# mainboard6.net
KiCad netlist of a schematic drawn in EAGLE
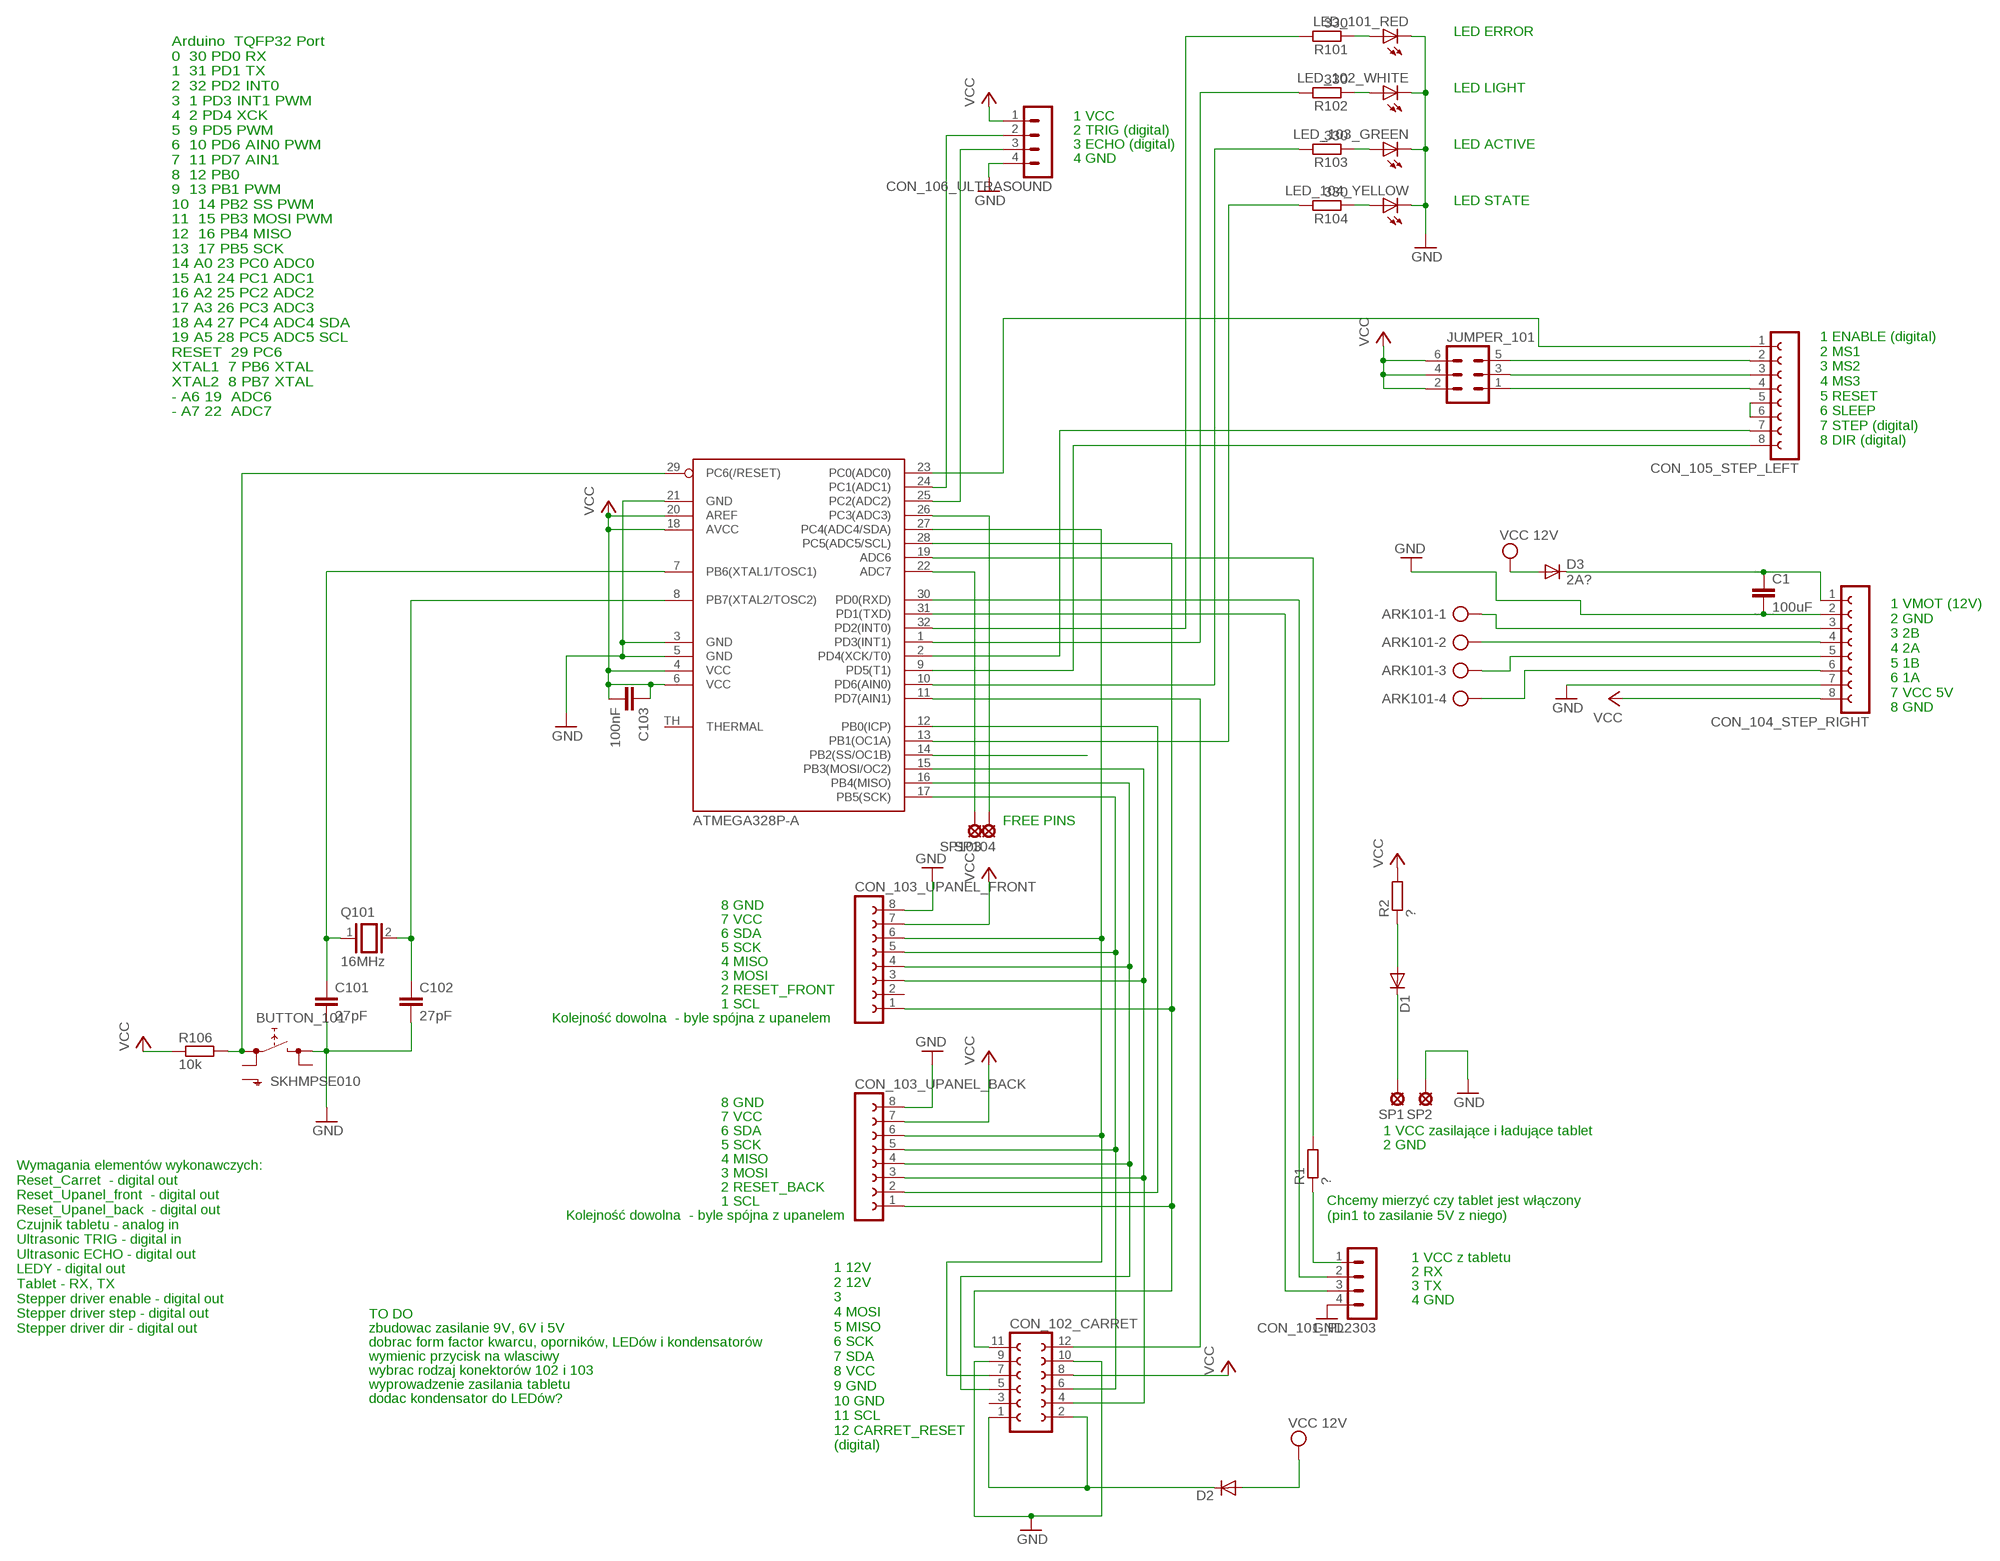
[diagram p0: schematic, sheet 1]

(export (version "E")
  (design (tool "Eeschema 10.0.6"))
  (components
    (comp (ref "ARK101")
      (value "AK300/4")
      (footprint "eagle-import:AK300_4")
      (libsource (lib "eagle-import") (part "AK300/4"))
    )
    (comp (ref "ATMEGA328P-A")
      (value "MEGA8-MI")
      (footprint "eagle-import:MLF32-TH")
      (libsource (lib "eagle-import") (part "MEGA8-MI"))
    )
    (comp (ref "BUTTON_101")
      (value "SKHMPSE010")
      (footprint "eagle-import:SKHMPXE010")
      (libsource (lib "eagle-import") (part "SKHMPE010S"))
    )
    (comp (ref "C1")
      (value "100uF")
      (footprint "eagle-import:C0805")
      (libsource (lib "eagle-import") (part "C"))
    )
    (comp (ref "C101")
      (value "27pF")
      (footprint "eagle-import:C5B5")
      (libsource (lib "eagle-import") (part "C5/5"))
    )
    (comp (ref "C102")
      (value "27pF")
      (footprint "eagle-import:C5B5")
      (libsource (lib "eagle-import") (part "C5/5"))
    )
    (comp (ref "C103")
      (value "100nF")
      (footprint "eagle-import:C5B5")
      (libsource (lib "eagle-import") (part "C5/5"))
    )
    (comp (ref "CON_101_PL2303")
      (value "MA04-1")
      (footprint "eagle-import:MA04-1")
      (libsource (lib "eagle-import") (part "MA04-1"))
    )
    (comp (ref "CON_102_CARRET")
      (value "FE06-2")
      (footprint "eagle-import:FE06-2")
      (libsource (lib "eagle-import") (part "FE06-2"))
    )
    (comp (ref "CON_103_UPANEL_BACK")
      (value "FE08-1")
      (footprint "eagle-import:FE08")
      (libsource (lib "eagle-import") (part "FE08-1"))
    )
    (comp (ref "CON_103_UPANEL_FRONT")
      (value "FE08-1")
      (footprint "eagle-import:FE08")
      (libsource (lib "eagle-import") (part "FE08-1"))
    )
    (comp (ref "CON_104_STEP_RIGHT")
      (value "FE08-1")
      (footprint "eagle-import:FE08")
      (libsource (lib "eagle-import") (part "FE08-1"))
    )
    (comp (ref "CON_105_STEP_LEFT")
      (value "FE08-1")
      (footprint "eagle-import:FE08")
      (libsource (lib "eagle-import") (part "FE08-1"))
    )
    (comp (ref "CON_106_ULTRASOUND")
      (value "MA04-1")
      (footprint "eagle-import:MA04-1")
      (libsource (lib "eagle-import") (part "MA04-1"))
    )
    (comp (ref "D1")
      (value "1N5060GP")
      (footprint "eagle-import:DO15-12")
      (libsource (lib "eagle-import") (part "1N5060GP"))
    )
    (comp (ref "D2")
      (value "1N5060GP")
      (footprint "eagle-import:DO15-12")
      (libsource (lib "eagle-import") (part "1N5060GP"))
    )
    (comp (ref "D3")
      (value "2A?")
      (footprint "eagle-import:DO15-12")
      (libsource (lib "eagle-import") (part "1N5060GP"))
    )
    (comp (ref "JUMPER_101")
      (value "MA03-2")
      (footprint "eagle-import:MA03-2")
      (libsource (lib "eagle-import") (part "MA03-2"))
    )
    (comp (ref "LED_101_RED")
      (value "LEDCHIPLED_1206")
      (footprint "eagle-import:CHIPLED_1206")
      (libsource (lib "eagle-import") (part "LEDCHIPLED_1206"))
    )
    (comp (ref "LED_102_WHITE")
      (value "LEDCHIPLED_1206")
      (footprint "eagle-import:CHIPLED_1206")
      (libsource (lib "eagle-import") (part "LEDCHIPLED_1206"))
    )
    (comp (ref "LED_103_GREEN")
      (value "LEDCHIPLED_1206")
      (footprint "eagle-import:CHIPLED_1206")
      (libsource (lib "eagle-import") (part "LEDCHIPLED_1206"))
    )
    (comp (ref "LED_104_YELLOW")
      (value "LEDCHIPLED_1206")
      (footprint "eagle-import:CHIPLED_1206")
      (libsource (lib "eagle-import") (part "LEDCHIPLED_1206"))
    )
    (comp (ref "Q101")
      (value "16MHz")
      (footprint "eagle-import:QS")
      (libsource (lib "eagle-import") (part "XTAL/S"))
    )
    (comp (ref "R1")
      (value "?")
      (footprint "eagle-import:P0613_15")
      (libsource (lib "eagle-import") (part "R-EU_0613/15"))
    )
    (comp (ref "R2")
      (value "?")
      (footprint "eagle-import:P0613_15")
      (libsource (lib "eagle-import") (part "R-EU_0613/15"))
    )
    (comp (ref "R101")
      (value "330")
      (footprint "eagle-import:M0805")
      (libsource (lib "eagle-import") (part "R-EU_M0805"))
    )
    (comp (ref "R102")
      (value "330")
      (footprint "eagle-import:M0805")
      (libsource (lib "eagle-import") (part "R-EU_M0805"))
    )
    (comp (ref "R103")
      (value "330")
      (footprint "eagle-import:M0805")
      (libsource (lib "eagle-import") (part "R-EU_M0805"))
    )
    (comp (ref "R104")
      (value "330")
      (footprint "eagle-import:M0805")
      (libsource (lib "eagle-import") (part "R-EU_M0805"))
    )
    (comp (ref "R106")
      (value "10k")
      (footprint "eagle-import:M3516")
      (libsource (lib "eagle-import") (part "R-EU_M3516"))
    )
    (comp (ref "SP1")
      (value "LSP11")
      (footprint "eagle-import:LSP11")
      (libsource (lib "eagle-import") (part "LSP11"))
    )
    (comp (ref "SP2")
      (value "LSP11")
      (footprint "eagle-import:LSP11")
      (libsource (lib "eagle-import") (part "LSP11"))
    )
    (comp (ref "SP103")
      (value "LSP11")
      (footprint "eagle-import:LSP11")
      (libsource (lib "eagle-import") (part "LSP11"))
    )
    (comp (ref "SP104")
      (value "LSP11")
      (footprint "eagle-import:LSP11")
      (libsource (lib "eagle-import") (part "LSP11"))
    )
  )
  (nets
    (net (code "1") (name "GND") (class "Default")
      (node (ref "ATMEGA328P-A") (pin "21") (pinfunction "GND_21") (pintype "power_in"))
      (node (ref "ATMEGA328P-A") (pin "3") (pinfunction "GND_3") (pintype "power_in"))
      (node (ref "ATMEGA328P-A") (pin "5") (pinfunction "GND_5") (pintype "power_in"))
      (node (ref "BUTTON_101") (pin "3") (pinfunction "2.1_3") (pintype "passive"))
      (node (ref "C1") (pin "2") (pinfunction "2_2") (pintype "passive"))
      (node (ref "C101") (pin "2") (pinfunction "2_2") (pintype "passive"))
      (node (ref "C102") (pin "2") (pinfunction "2_2") (pintype "passive"))
      (node (ref "CON_101_PL2303") (pin "4") (pinfunction "4_4") (pintype "passive"))
      (node (ref "CON_102_CARRET") (pin "10") (pinfunction "10_10") (pintype "passive"))
      (node (ref "CON_102_CARRET") (pin "9") (pinfunction "9_9") (pintype "passive"))
      (node (ref "CON_103_UPANEL_BACK") (pin "8") (pinfunction "8_8") (pintype "passive"))
      (node (ref "CON_103_UPANEL_FRONT") (pin "8") (pinfunction "8_8") (pintype "passive"))
      (node (ref "CON_104_STEP_RIGHT") (pin "2") (pinfunction "2_2") (pintype "passive"))
      (node (ref "CON_104_STEP_RIGHT") (pin "7") (pinfunction "7_7") (pintype "passive"))
      (node (ref "CON_106_ULTRASOUND") (pin "4") (pinfunction "4_4") (pintype "passive"))
      (node (ref "LED_101_RED") (pin "C") (pinfunction "C_C") (pintype "passive"))
      (node (ref "LED_102_WHITE") (pin "C") (pinfunction "C_C") (pintype "passive"))
      (node (ref "LED_103_GREEN") (pin "C") (pinfunction "C_C") (pintype "passive"))
      (node (ref "LED_104_YELLOW") (pin "C") (pinfunction "C_C") (pintype "passive"))
      (node (ref "SP2") (pin "MP") (pinfunction "MP_MP") (pintype "passive"))
    )
    (net (code "2") (name "Net-(ARK101A-KL)") (class "Default")
      (node (ref "ARK101") (pin "1") (pinfunction "KL_1") (pintype "passive"))
      (node (ref "CON_104_STEP_RIGHT") (pin "3") (pinfunction "3_3") (pintype "passive"))
    )
    (net (code "3") (name "Net-(ARK101B-KL)") (class "Default")
      (node (ref "ARK101") (pin "2") (pinfunction "KL_2") (pintype "passive"))
      (node (ref "CON_104_STEP_RIGHT") (pin "4") (pinfunction "4_4") (pintype "passive"))
    )
    (net (code "4") (name "Net-(ARK101C-KL)") (class "Default")
      (node (ref "ARK101") (pin "3") (pinfunction "KL_3") (pintype "passive"))
      (node (ref "CON_104_STEP_RIGHT") (pin "5") (pinfunction "5_5") (pintype "passive"))
    )
    (net (code "5") (name "Net-(ARK101D-KL)") (class "Default")
      (node (ref "ARK101") (pin "4") (pinfunction "KL_4") (pintype "passive"))
      (node (ref "CON_104_STEP_RIGHT") (pin "6") (pinfunction "6_6") (pintype "passive"))
    )
    (net (code "6") (name "Net-(ATMEGA328P-A-ADC6)") (class "Default")
      (node (ref "ATMEGA328P-A") (pin "19") (pinfunction "ADC6_19") (pintype "bidirectional"))
      (node (ref "R1") (pin "2") (pinfunction "2_2") (pintype "passive"))
    )
    (net (code "7") (name "Net-(ATMEGA328P-A-ADC7)") (class "Default")
      (node (ref "ATMEGA328P-A") (pin "22") (pinfunction "ADC7_22") (pintype "bidirectional"))
      (node (ref "SP103") (pin "MP") (pinfunction "MP_MP") (pintype "passive"))
    )
    (net (code "8") (name "Net-(ATMEGA328P-A-PB0(ICP))") (class "Default")
      (node (ref "ATMEGA328P-A") (pin "12") (pinfunction "PB0(ICP)_12") (pintype "bidirectional"))
      (node (ref "CON_103_UPANEL_BACK") (pin "2") (pinfunction "2_2") (pintype "passive"))
    )
    (net (code "9") (name "Net-(ATMEGA328P-A-PB1(OC1A))") (class "Default")
      (node (ref "ATMEGA328P-A") (pin "13") (pinfunction "PB1(OC1A)_13") (pintype "bidirectional"))
      (node (ref "R104") (pin "2") (pinfunction "2_2") (pintype "passive"))
    )
    (net (code "10") (name "Net-(ATMEGA328P-A-PB3(MOSI{slash}OC2))") (class "Default")
      (node (ref "ATMEGA328P-A") (pin "15") (pinfunction "PB3(MOSI/OC2)_15") (pintype "bidirectional"))
      (node (ref "CON_102_CARRET") (pin "4") (pinfunction "4_4") (pintype "passive"))
      (node (ref "CON_103_UPANEL_BACK") (pin "3") (pinfunction "3_3") (pintype "passive"))
      (node (ref "CON_103_UPANEL_FRONT") (pin "3") (pinfunction "3_3") (pintype "passive"))
    )
    (net (code "11") (name "Net-(ATMEGA328P-A-PB4(MISO))") (class "Default")
      (node (ref "ATMEGA328P-A") (pin "16") (pinfunction "PB4(MISO)_16") (pintype "bidirectional"))
      (node (ref "CON_102_CARRET") (pin "5") (pinfunction "5_5") (pintype "passive"))
      (node (ref "CON_103_UPANEL_BACK") (pin "4") (pinfunction "4_4") (pintype "passive"))
      (node (ref "CON_103_UPANEL_FRONT") (pin "4") (pinfunction "4_4") (pintype "passive"))
    )
    (net (code "12") (name "Net-(ATMEGA328P-A-PB5(SCK))") (class "Default")
      (node (ref "ATMEGA328P-A") (pin "17") (pinfunction "PB5(SCK)_17") (pintype "bidirectional"))
      (node (ref "CON_102_CARRET") (pin "6") (pinfunction "6_6") (pintype "passive"))
      (node (ref "CON_103_UPANEL_BACK") (pin "5") (pinfunction "5_5") (pintype "passive"))
      (node (ref "CON_103_UPANEL_FRONT") (pin "5") (pinfunction "5_5") (pintype "passive"))
    )
    (net (code "13") (name "Net-(ATMEGA328P-A-PB6(XTAL1{slash}TOSC1))") (class "Default")
      (node (ref "ATMEGA328P-A") (pin "7") (pinfunction "PB6(XTAL1/TOSC1)_7") (pintype "bidirectional"))
      (node (ref "C101") (pin "1") (pinfunction "1_1") (pintype "passive"))
      (node (ref "Q101") (pin "1") (pinfunction "1_1") (pintype "passive"))
    )
    (net (code "14") (name "Net-(ATMEGA328P-A-PB7(XTAL2{slash}TOSC2))") (class "Default")
      (node (ref "ATMEGA328P-A") (pin "8") (pinfunction "PB7(XTAL2/TOSC2)_8") (pintype "bidirectional"))
      (node (ref "C102") (pin "1") (pinfunction "1_1") (pintype "passive"))
      (node (ref "Q101") (pin "2") (pinfunction "2_2") (pintype "passive"))
    )
    (net (code "15") (name "Net-(ATMEGA328P-A-PC0(ADC0))") (class "Default")
      (node (ref "ATMEGA328P-A") (pin "23") (pinfunction "PC0(ADC0)_23") (pintype "bidirectional"))
      (node (ref "CON_105_STEP_LEFT") (pin "1") (pinfunction "1_1") (pintype "passive"))
    )
    (net (code "16") (name "Net-(ATMEGA328P-A-PC1(ADC1))") (class "Default")
      (node (ref "ATMEGA328P-A") (pin "24") (pinfunction "PC1(ADC1)_24") (pintype "bidirectional"))
      (node (ref "CON_106_ULTRASOUND") (pin "2") (pinfunction "2_2") (pintype "passive"))
    )
    (net (code "17") (name "Net-(ATMEGA328P-A-PC2(ADC2))") (class "Default")
      (node (ref "ATMEGA328P-A") (pin "25") (pinfunction "PC2(ADC2)_25") (pintype "bidirectional"))
      (node (ref "CON_106_ULTRASOUND") (pin "3") (pinfunction "3_3") (pintype "passive"))
    )
    (net (code "18") (name "Net-(ATMEGA328P-A-PC3(ADC3))") (class "Default")
      (node (ref "ATMEGA328P-A") (pin "26") (pinfunction "PC3(ADC3)_26") (pintype "bidirectional"))
      (node (ref "SP104") (pin "MP") (pinfunction "MP_MP") (pintype "passive"))
    )
    (net (code "19") (name "Net-(ATMEGA328P-A-PC4(ADC4{slash}SDA))") (class "Default")
      (node (ref "ATMEGA328P-A") (pin "27") (pinfunction "PC4(ADC4/SDA)_27") (pintype "bidirectional"))
      (node (ref "CON_102_CARRET") (pin "7") (pinfunction "7_7") (pintype "passive"))
      (node (ref "CON_103_UPANEL_BACK") (pin "6") (pinfunction "6_6") (pintype "passive"))
      (node (ref "CON_103_UPANEL_FRONT") (pin "6") (pinfunction "6_6") (pintype "passive"))
    )
    (net (code "20") (name "Net-(ATMEGA328P-A-PC5(ADC5{slash}SCL))") (class "Default")
      (node (ref "ATMEGA328P-A") (pin "28") (pinfunction "PC5(ADC5/SCL)_28") (pintype "bidirectional"))
      (node (ref "CON_102_CARRET") (pin "11") (pinfunction "11_11") (pintype "passive"))
      (node (ref "CON_103_UPANEL_BACK") (pin "1") (pinfunction "1_1") (pintype "passive"))
      (node (ref "CON_103_UPANEL_FRONT") (pin "1") (pinfunction "1_1") (pintype "passive"))
    )
    (net (code "21") (name "Net-(ATMEGA328P-A-PC6({slash}RESET))") (class "Default")
      (node (ref "ATMEGA328P-A") (pin "29") (pinfunction "PC6(/RESET)_29") (pintype "bidirectional"))
      (node (ref "BUTTON_101") (pin "1") (pinfunction "1.1_1") (pintype "passive"))
      (node (ref "R106") (pin "2") (pinfunction "2_2") (pintype "passive"))
    )
    (net (code "22") (name "Net-(ATMEGA328P-A-PD0(RXD))") (class "Default")
      (node (ref "ATMEGA328P-A") (pin "30") (pinfunction "PD0(RXD)_30") (pintype "bidirectional"))
      (node (ref "CON_101_PL2303") (pin "2") (pinfunction "2_2") (pintype "passive"))
    )
    (net (code "23") (name "Net-(ATMEGA328P-A-PD1(TXD))") (class "Default")
      (node (ref "ATMEGA328P-A") (pin "31") (pinfunction "PD1(TXD)_31") (pintype "bidirectional"))
      (node (ref "CON_101_PL2303") (pin "3") (pinfunction "3_3") (pintype "passive"))
    )
    (net (code "24") (name "Net-(ATMEGA328P-A-PD2(INT0))") (class "Default")
      (node (ref "ATMEGA328P-A") (pin "32") (pinfunction "PD2(INT0)_32") (pintype "bidirectional"))
      (node (ref "R101") (pin "2") (pinfunction "2_2") (pintype "passive"))
    )
    (net (code "25") (name "Net-(ATMEGA328P-A-PD3(INT1))") (class "Default")
      (node (ref "ATMEGA328P-A") (pin "1") (pinfunction "PD3(INT1)_1") (pintype "bidirectional"))
      (node (ref "R102") (pin "2") (pinfunction "2_2") (pintype "passive"))
    )
    (net (code "26") (name "Net-(ATMEGA328P-A-PD4(XCK{slash}T0))") (class "Default")
      (node (ref "ATMEGA328P-A") (pin "2") (pinfunction "PD4(XCK/T0)_2") (pintype "bidirectional"))
      (node (ref "CON_105_STEP_LEFT") (pin "7") (pinfunction "7_7") (pintype "passive"))
    )
    (net (code "27") (name "Net-(ATMEGA328P-A-PD5(T1))") (class "Default")
      (node (ref "ATMEGA328P-A") (pin "9") (pinfunction "PD5(T1)_9") (pintype "bidirectional"))
      (node (ref "CON_105_STEP_LEFT") (pin "8") (pinfunction "8_8") (pintype "passive"))
    )
    (net (code "28") (name "Net-(ATMEGA328P-A-PD6(AIN0))") (class "Default")
      (node (ref "ATMEGA328P-A") (pin "10") (pinfunction "PD6(AIN0)_10") (pintype "bidirectional"))
      (node (ref "R103") (pin "2") (pinfunction "2_2") (pintype "passive"))
    )
    (net (code "29") (name "Net-(ATMEGA328P-A-PD7(AIN1))") (class "Default")
      (node (ref "ATMEGA328P-A") (pin "11") (pinfunction "PD7(AIN1)_11") (pintype "bidirectional"))
      (node (ref "CON_102_CARRET") (pin "12") (pinfunction "12_12") (pintype "passive"))
    )
    (net (code "30") (name "Net-(C1-Pad1)") (class "Default")
      (node (ref "C1") (pin "1") (pinfunction "1_1") (pintype "passive"))
      (node (ref "CON_104_STEP_RIGHT") (pin "1") (pinfunction "1_1") (pintype "passive"))
      (node (ref "D3") (pin "C") (pinfunction "C_C") (pintype "passive"))
    )
    (net (code "31") (name "Net-(CON_102_CARRET-Pad1)") (class "Default")
      (node (ref "CON_102_CARRET") (pin "1") (pinfunction "1_1") (pintype "passive"))
      (node (ref "CON_102_CARRET") (pin "2") (pinfunction "2_2") (pintype "passive"))
      (node (ref "D2") (pin "C") (pinfunction "C_C") (pintype "passive"))
    )
    (net (code "32") (name "Net-(CON_105_STEP_LEFT-Pad2)") (class "Default")
      (node (ref "CON_105_STEP_LEFT") (pin "2") (pinfunction "2_2") (pintype "passive"))
      (node (ref "JUMPER_101") (pin "5") (pinfunction "5_5") (pintype "passive"))
    )
    (net (code "33") (name "Net-(CON_105_STEP_LEFT-Pad3)") (class "Default")
      (node (ref "CON_105_STEP_LEFT") (pin "3") (pinfunction "3_3") (pintype "passive"))
      (node (ref "JUMPER_101") (pin "3") (pinfunction "3_3") (pintype "passive"))
    )
    (net (code "34") (name "Net-(CON_105_STEP_LEFT-Pad4)") (class "Default")
      (node (ref "CON_105_STEP_LEFT") (pin "4") (pinfunction "4_4") (pintype "passive"))
      (node (ref "JUMPER_101") (pin "1") (pinfunction "1_1") (pintype "passive"))
    )
    (net (code "35") (name "Net-(CON_105_STEP_LEFT-Pad5)") (class "Default")
      (node (ref "CON_105_STEP_LEFT") (pin "5") (pinfunction "5_5") (pintype "passive"))
      (node (ref "CON_105_STEP_LEFT") (pin "6") (pinfunction "6_6") (pintype "passive"))
    )
    (net (code "36") (name "Net-(D1-PadA)") (class "Default")
      (node (ref "D1") (pin "A") (pinfunction "A_A") (pintype "passive"))
      (node (ref "R2") (pin "1") (pinfunction "1_1") (pintype "passive"))
    )
    (net (code "37") (name "Net-(D1-PadC)") (class "Default")
      (node (ref "D1") (pin "C") (pinfunction "C_C") (pintype "passive"))
      (node (ref "SP1") (pin "MP") (pinfunction "MP_MP") (pintype "passive"))
    )
    (net (code "38") (name "Net-(LED_101_RED-PadA)") (class "Default")
      (node (ref "LED_101_RED") (pin "A") (pinfunction "A_A") (pintype "passive"))
      (node (ref "R101") (pin "1") (pinfunction "1_1") (pintype "passive"))
    )
    (net (code "39") (name "Net-(LED_102_WHITE-PadA)") (class "Default")
      (node (ref "LED_102_WHITE") (pin "A") (pinfunction "A_A") (pintype "passive"))
      (node (ref "R102") (pin "1") (pinfunction "1_1") (pintype "passive"))
    )
    (net (code "40") (name "Net-(LED_103_GREEN-PadA)") (class "Default")
      (node (ref "LED_103_GREEN") (pin "A") (pinfunction "A_A") (pintype "passive"))
      (node (ref "R103") (pin "1") (pinfunction "1_1") (pintype "passive"))
    )
    (net (code "41") (name "Net-(LED_104_YELLOW-PadA)") (class "Default")
      (node (ref "LED_104_YELLOW") (pin "A") (pinfunction "A_A") (pintype "passive"))
      (node (ref "R104") (pin "1") (pinfunction "1_1") (pintype "passive"))
    )
    (net (code "42") (name "VCC") (class "Default")
      (node (ref "ATMEGA328P-A") (pin "18") (pinfunction "AVCC_18") (pintype "power_in"))
      (node (ref "ATMEGA328P-A") (pin "20") (pinfunction "AREF_20") (pintype "passive"))
      (node (ref "ATMEGA328P-A") (pin "4") (pinfunction "VCC_4") (pintype "power_in"))
      (node (ref "ATMEGA328P-A") (pin "6") (pinfunction "VCC_6") (pintype "power_in"))
      (node (ref "C103") (pin "1") (pinfunction "1_1") (pintype "passive"))
      (node (ref "C103") (pin "2") (pinfunction "2_2") (pintype "passive"))
      (node (ref "CON_102_CARRET") (pin "8") (pinfunction "8_8") (pintype "passive"))
      (node (ref "CON_103_UPANEL_BACK") (pin "7") (pinfunction "7_7") (pintype "passive"))
      (node (ref "CON_103_UPANEL_FRONT") (pin "7") (pinfunction "7_7") (pintype "passive"))
      (node (ref "CON_104_STEP_RIGHT") (pin "8") (pinfunction "8_8") (pintype "passive"))
      (node (ref "CON_106_ULTRASOUND") (pin "1") (pinfunction "1_1") (pintype "passive"))
      (node (ref "D2") (pin "A") (pinfunction "A_A") (pintype "passive"))
      (node (ref "D3") (pin "A") (pinfunction "A_A") (pintype "passive"))
      (node (ref "JUMPER_101") (pin "2") (pinfunction "2_2") (pintype "passive"))
      (node (ref "JUMPER_101") (pin "4") (pinfunction "4_4") (pintype "passive"))
      (node (ref "JUMPER_101") (pin "6") (pinfunction "6_6") (pintype "passive"))
      (node (ref "R106") (pin "1") (pinfunction "1_1") (pintype "passive"))
      (node (ref "R2") (pin "2") (pinfunction "2_2") (pintype "passive"))
    )
    (net (code "43") (name "unconnected-(ATMEGA328P-A-PB2(SS{slash}OC1B)-Pad14)") (class "Default")
      (node (ref "ATMEGA328P-A") (pin "14") (pinfunction "PB2(SS/OC1B)_14") (pintype "bidirectional"))
    )
    (net (code "44") (name "unconnected-(ATMEGA328P-A-THERMAL-PadTH)") (class "Default")
      (node (ref "ATMEGA328P-A") (pin "TH") (pinfunction "THERMAL_TH") (pintype "passive"))
    )
    (net (code "45") (name "unconnected-(BUTTON_101-1.2-Pad2)") (class "Default")
      (node (ref "BUTTON_101") (pin "2") (pinfunction "1.2_2") (pintype "passive"))
    )
    (net (code "46") (name "unconnected-(BUTTON_101-2.2-Pad4)") (class "Default")
      (node (ref "BUTTON_101") (pin "4") (pinfunction "2.2_4") (pintype "passive"))
    )
    (net (code "47") (name "unconnected-(BUTTON_101-SH-Pad5)") (class "Default")
      (node (ref "BUTTON_101") (pin "5") (pinfunction "SH_5") (pintype "passive"))
    )
    (net (code "48") (name "unconnected-(CON_101_PL2303-Pad1)") (class "Default")
      (node (ref "CON_101_PL2303") (pin "1") (pinfunction "1_1") (pintype "passive"))
    )
    (net (code "49") (name "unconnected-(CON_102_CARRET-Pad3)") (class "Default")
      (node (ref "CON_102_CARRET") (pin "3") (pinfunction "3_3") (pintype "passive"))
    )
    (net (code "50") (name "unconnected-(CON_103_UPANEL_FRONT-Pad2)") (class "Default")
      (node (ref "CON_103_UPANEL_FRONT") (pin "2") (pinfunction "2_2") (pintype "passive"))
    )
    (net (code "51") (name "unconnected-(R1-Pad1)") (class "Default")
      (node (ref "R1") (pin "1") (pinfunction "1_1") (pintype "passive"))
    )
  )
)
